# mcp3551_adc_module.net
KiCad netlist of a schematic drawn in EAGLE
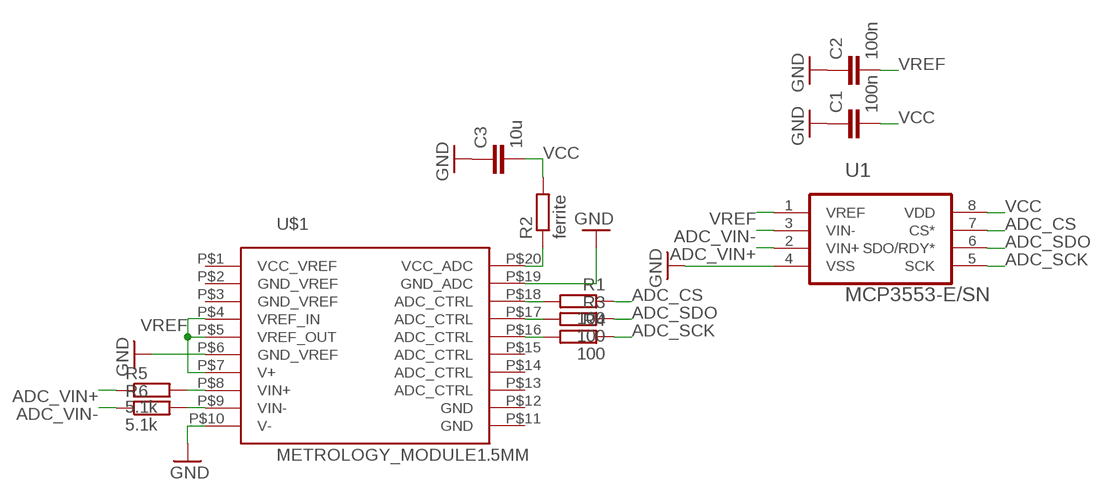
[diagram p0: schematic, sheet 1]

(export (version "E")
  (design (tool "Eeschema 10.0.6"))
  (components
    (comp (ref "C1")
      (value "100n")
      (footprint "eagle-import:C0603")
      (libsource (lib "eagle-import") (part "C-EUC0603"))
    )
    (comp (ref "C2")
      (value "100n")
      (footprint "eagle-import:C0603")
      (libsource (lib "eagle-import") (part "C-EUC0603"))
    )
    (comp (ref "C3")
      (value "10u")
      (footprint "eagle-import:C0805")
      (libsource (lib "eagle-import") (part "C-EUC0805"))
    )
    (comp (ref "R1")
      (value "100")
      (footprint "eagle-import:R0603")
      (libsource (lib "eagle-import") (part "R-EU_R0603"))
    )
    (comp (ref "R2")
      (value "ferrite")
      (footprint "eagle-import:R0805")
      (libsource (lib "eagle-import") (part "R-EU_R0805"))
    )
    (comp (ref "R3")
      (value "100")
      (footprint "eagle-import:R0603")
      (libsource (lib "eagle-import") (part "R-EU_R0603"))
    )
    (comp (ref "R4")
      (value "100")
      (footprint "eagle-import:R0603")
      (libsource (lib "eagle-import") (part "R-EU_R0603"))
    )
    (comp (ref "R5")
      (value "5.1k")
      (footprint "eagle-import:R0805")
      (libsource (lib "eagle-import") (part "R-EU_R0805"))
    )
    (comp (ref "R6")
      (value "5.1k")
      (footprint "eagle-import:R0805")
      (libsource (lib "eagle-import") (part "R-EU_R0805"))
    )
    (comp (ref "U$1")
      (value "METROLOGY_MODULE1.5MM")
      (footprint "eagle-import:METROLOGY_MODULE_1.5MM_HOLE")
      (libsource (lib "eagle-import") (part "METROLOGY_MODULE1.5MM"))
    )
    (comp (ref "U1")
      (value "MCP3553-E/SN")
      (footprint "eagle-import:SOIC127P600X175-8N")
      (libsource (lib "eagle-import") (part "MCP3553-E/SN"))
    )
  )
  (nets
    (net (code "1") (name "/ADC_CS") (class "Default")
      (node (ref "R1") (pin "1") (pinfunction "1_1") (pintype "passive"))
      (node (ref "U1") (pin "7") (pinfunction "CS*_7") (pintype "input"))
    )
    (net (code "2") (name "/ADC_SCK") (class "Default")
      (node (ref "R4") (pin "1") (pinfunction "1_1") (pintype "passive"))
      (node (ref "U1") (pin "5") (pinfunction "SCK_5") (pintype "input"))
    )
    (net (code "3") (name "/ADC_SDO") (class "Default")
      (node (ref "R3") (pin "1") (pinfunction "1_1") (pintype "passive"))
      (node (ref "U1") (pin "6") (pinfunction "SDO/RDY*_6") (pintype "output"))
    )
    (net (code "4") (name "/ADC_VIN+") (class "Default")
      (node (ref "R5") (pin "1") (pinfunction "1_1") (pintype "passive"))
      (node (ref "U1") (pin "2") (pinfunction "VIN+_2") (pintype "input"))
    )
    (net (code "5") (name "/ADC_VIN-") (class "Default")
      (node (ref "R6") (pin "1") (pinfunction "1_1") (pintype "passive"))
      (node (ref "U1") (pin "3") (pinfunction "VIN-_3") (pintype "input"))
    )
    (net (code "6") (name "/VCC") (class "Default")
      (node (ref "C1") (pin "2") (pinfunction "2_2") (pintype "passive"))
      (node (ref "C3") (pin "2") (pinfunction "2_2") (pintype "passive"))
      (node (ref "R2") (pin "2") (pinfunction "2_2") (pintype "passive"))
      (node (ref "U1") (pin "8") (pinfunction "VDD_8") (pintype "power_in"))
    )
    (net (code "7") (name "/VREF") (class "Default")
      (node (ref "C2") (pin "2") (pinfunction "2_2") (pintype "passive"))
      (node (ref "U$1") (pin "P$4") (pinfunction "VREF_IN_P$4") (pintype "bidirectional"))
      (node (ref "U$1") (pin "P$5") (pinfunction "VREF_OUT_P$5") (pintype "bidirectional"))
      (node (ref "U$1") (pin "P$7") (pinfunction "V+_P$7") (pintype "bidirectional"))
      (node (ref "U1") (pin "1") (pinfunction "VREF_1") (pintype "input"))
    )
    (net (code "8") (name "GND") (class "Default")
      (node (ref "C1") (pin "1") (pinfunction "1_1") (pintype "passive"))
      (node (ref "C2") (pin "1") (pinfunction "1_1") (pintype "passive"))
      (node (ref "C3") (pin "1") (pinfunction "1_1") (pintype "passive"))
      (node (ref "U$1") (pin "P$10") (pinfunction "V-_P$10") (pintype "bidirectional"))
      (node (ref "U$1") (pin "P$19") (pinfunction "GND_ADC_P$19") (pintype "bidirectional"))
      (node (ref "U$1") (pin "P$6") (pinfunction "GND_VREF_P$6") (pintype "bidirectional"))
      (node (ref "U1") (pin "4") (pinfunction "VSS_4") (pintype "passive"))
    )
    (net (code "9") (name "Net-(R1-Pad2)") (class "Default")
      (node (ref "R1") (pin "2") (pinfunction "2_2") (pintype "passive"))
      (node (ref "U$1") (pin "P$18") (pinfunction "ADC_CTRL_P$18") (pintype "bidirectional"))
    )
    (net (code "10") (name "Net-(R3-Pad2)") (class "Default")
      (node (ref "R3") (pin "2") (pinfunction "2_2") (pintype "passive"))
      (node (ref "U$1") (pin "P$17") (pinfunction "ADC_CTRL_P$17") (pintype "bidirectional"))
    )
    (net (code "11") (name "Net-(R4-Pad2)") (class "Default")
      (node (ref "R4") (pin "2") (pinfunction "2_2") (pintype "passive"))
      (node (ref "U$1") (pin "P$16") (pinfunction "ADC_CTRL_P$16") (pintype "bidirectional"))
    )
    (net (code "12") (name "Net-(U$1-VCC_ADC)") (class "Default")
      (node (ref "R2") (pin "1") (pinfunction "1_1") (pintype "passive"))
      (node (ref "U$1") (pin "P$20") (pinfunction "VCC_ADC_P$20") (pintype "bidirectional"))
    )
    (net (code "13") (name "Net-(U$1-VIN+)") (class "Default")
      (node (ref "R5") (pin "2") (pinfunction "2_2") (pintype "passive"))
      (node (ref "U$1") (pin "P$8") (pinfunction "VIN+_P$8") (pintype "bidirectional"))
    )
    (net (code "14") (name "Net-(U$1-VIN-)") (class "Default")
      (node (ref "R6") (pin "2") (pinfunction "2_2") (pintype "passive"))
      (node (ref "U$1") (pin "P$9") (pinfunction "VIN-_P$9") (pintype "bidirectional"))
    )
    (net (code "15") (name "unconnected-(U$1-ADC_CTRL-PadP$13)") (class "Default")
      (node (ref "U$1") (pin "P$13") (pinfunction "ADC_CTRL_P$13") (pintype "bidirectional"))
    )
    (net (code "16") (name "unconnected-(U$1-ADC_CTRL-PadP$14)") (class "Default")
      (node (ref "U$1") (pin "P$14") (pinfunction "ADC_CTRL_P$14") (pintype "bidirectional"))
    )
    (net (code "17") (name "unconnected-(U$1-ADC_CTRL-PadP$15)") (class "Default")
      (node (ref "U$1") (pin "P$15") (pinfunction "ADC_CTRL_P$15") (pintype "bidirectional"))
    )
    (net (code "18") (name "unconnected-(U$1-GND-PadP$11)") (class "Default")
      (node (ref "U$1") (pin "P$11") (pinfunction "GND_P$11") (pintype "bidirectional"))
    )
    (net (code "19") (name "unconnected-(U$1-GND-PadP$12)") (class "Default")
      (node (ref "U$1") (pin "P$12") (pinfunction "GND_P$12") (pintype "bidirectional"))
    )
    (net (code "20") (name "unconnected-(U$1-GND_VREF-PadP$2)") (class "Default")
      (node (ref "U$1") (pin "P$2") (pinfunction "GND_VREF_P$2") (pintype "bidirectional"))
    )
    (net (code "21") (name "unconnected-(U$1-GND_VREF-PadP$3)") (class "Default")
      (node (ref "U$1") (pin "P$3") (pinfunction "GND_VREF_P$3") (pintype "bidirectional"))
    )
    (net (code "22") (name "unconnected-(U$1-VCC_VREF-PadP$1)") (class "Default")
      (node (ref "U$1") (pin "P$1") (pinfunction "VCC_VREF_P$1") (pintype "bidirectional"))
    )
  )
)
